# RGB_i2c_v2plusRTC.net
KiCad netlist of a schematic drawn in EAGLE
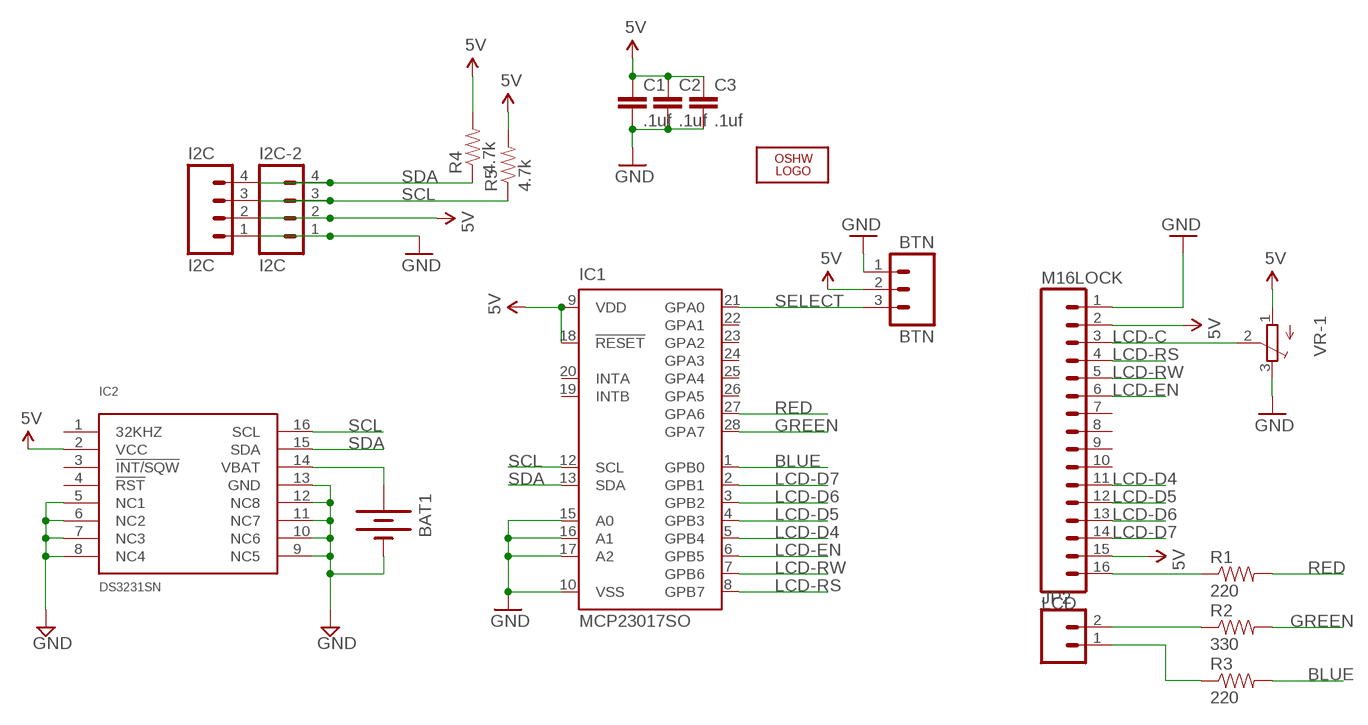
[diagram p0: schematic, sheet 1]

(export (version "E")
  (design (tool "Eeschema 10.0.6"))
  (components
    (comp (ref "BAT1")
      (value "BATTERY12MM")
      (footprint "eagle-import:BATTCON_12MM")
      (libsource (lib "eagle-import") (part "BATTERY12MM"))
    )
    (comp (ref "BTN")
      (value "BTN")
      (footprint "eagle-import:1X03_LOCK")
      (libsource (lib "eagle-import") (part "M03LOCK"))
    )
    (comp (ref "C1")
      (value ".1uf")
      (footprint "eagle-import:0805")
      (libsource (lib "eagle-import") (part "CAP0805"))
    )
    (comp (ref "C2")
      (value ".1uf")
      (footprint "eagle-import:0805")
      (libsource (lib "eagle-import") (part "CAP0805"))
    )
    (comp (ref "C3")
      (value ".1uf")
      (footprint "eagle-import:0805")
      (libsource (lib "eagle-import") (part "CAP0805"))
    )
    (comp (ref "I2C")
      (value "I2C")
      (footprint "eagle-import:1X04_LOCK")
      (libsource (lib "eagle-import") (part "M04LOCK"))
    )
    (comp (ref "I2C-2")
      (value "I2C")
      (footprint "eagle-import:1X04_LOCK")
      (libsource (lib "eagle-import") (part "M04LOCK"))
    )
    (comp (ref "IC1")
      (value "MCP23017SO")
      (footprint "eagle-import:SO28W")
      (libsource (lib "eagle-import") (part "MCP23017SO"))
    )
    (comp (ref "IC2")
      (value "DS3231SN")
      (footprint "eagle-import:SO16W")
      (libsource (lib "eagle-import") (part "DS3231SN"))
    )
    (comp (ref "JP2")
      (value "M02PTH")
      (footprint "eagle-import:1X02")
      (libsource (lib "eagle-import") (part "M02PTH"))
    )
    (comp (ref "LCD")
      (value "M16LOCK")
      (footprint "eagle-import:1X16_LOCK")
      (libsource (lib "eagle-import") (part "M16LOCK"))
    )
    (comp (ref "LOGO2")
      (value "OSHW_LOGO_10MILX0350-NT")
      (footprint "eagle-import:OSHW_10X350_NOTEXT")
      (libsource (lib "eagle-import") (part "OSHW_LOGO_10MILX0350-NT"))
    )
    (comp (ref "R1")
      (value "220")
      (footprint "eagle-import:0805")
      (libsource (lib "eagle-import") (part "RESISTOR0805-RES"))
    )
    (comp (ref "R2")
      (value "330")
      (footprint "eagle-import:0805")
      (libsource (lib "eagle-import") (part "RESISTOR0805-RES"))
    )
    (comp (ref "R3")
      (value "220")
      (footprint "eagle-import:0805")
      (libsource (lib "eagle-import") (part "RESISTOR0805-RES"))
    )
    (comp (ref "R4")
      (value "4.7k")
      (footprint "eagle-import:0805")
      (libsource (lib "eagle-import") (part "RESISTOR0805-RES"))
    )
    (comp (ref "R5")
      (value "4.7k")
      (footprint "eagle-import:0805")
      (libsource (lib "eagle-import") (part "RESISTOR0805-RES"))
    )
    (comp (ref "VR-1")
      (value "TRIMPOTTC33X")
      (footprint "eagle-import:TC33X")
      (libsource (lib "eagle-import") (part "TRIMPOTTC33X"))
    )
  )
  (nets
    (net (code "1") (name "/BLUE") (class "Default")
      (node (ref "IC1") (pin "1") (pinfunction "GPB0_1") (pintype "bidirectional"))
      (node (ref "R3") (pin "2") (pinfunction "2_2") (pintype "passive"))
    )
    (net (code "2") (name "/GREEN") (class "Default")
      (node (ref "IC1") (pin "28") (pinfunction "GPA7_28") (pintype "bidirectional"))
      (node (ref "R2") (pin "2") (pinfunction "2_2") (pintype "passive"))
    )
    (net (code "3") (name "/LCD-C") (class "Default")
      (node (ref "LCD") (pin "3") (pinfunction "3_3") (pintype "passive"))
      (node (ref "VR-1") (pin "2") (pinfunction "S_2") (pintype "passive"))
    )
    (net (code "4") (name "/LCD-D4") (class "Default")
      (node (ref "IC1") (pin "5") (pinfunction "GPB4_5") (pintype "bidirectional"))
      (node (ref "LCD") (pin "11") (pinfunction "11_11") (pintype "passive"))
    )
    (net (code "5") (name "/LCD-D5") (class "Default")
      (node (ref "IC1") (pin "4") (pinfunction "GPB3_4") (pintype "bidirectional"))
      (node (ref "LCD") (pin "12") (pinfunction "12_12") (pintype "passive"))
    )
    (net (code "6") (name "/LCD-D6") (class "Default")
      (node (ref "IC1") (pin "3") (pinfunction "GPB2_3") (pintype "bidirectional"))
      (node (ref "LCD") (pin "13") (pinfunction "13_13") (pintype "passive"))
    )
    (net (code "7") (name "/LCD-D7") (class "Default")
      (node (ref "IC1") (pin "2") (pinfunction "GPB1_2") (pintype "bidirectional"))
      (node (ref "LCD") (pin "14") (pinfunction "14_14") (pintype "passive"))
    )
    (net (code "8") (name "/LCD-EN") (class "Default")
      (node (ref "IC1") (pin "6") (pinfunction "GPB5_6") (pintype "bidirectional"))
      (node (ref "LCD") (pin "6") (pinfunction "6_6") (pintype "passive"))
    )
    (net (code "9") (name "/LCD-RS") (class "Default")
      (node (ref "IC1") (pin "8") (pinfunction "GPB7_8") (pintype "bidirectional"))
      (node (ref "LCD") (pin "4") (pinfunction "4_4") (pintype "passive"))
    )
    (net (code "10") (name "/LCD-RW") (class "Default")
      (node (ref "IC1") (pin "7") (pinfunction "GPB6_7") (pintype "bidirectional"))
      (node (ref "LCD") (pin "5") (pinfunction "5_5") (pintype "passive"))
    )
    (net (code "11") (name "/RED") (class "Default")
      (node (ref "IC1") (pin "27") (pinfunction "GPA6_27") (pintype "bidirectional"))
      (node (ref "R1") (pin "2") (pinfunction "2_2") (pintype "passive"))
    )
    (net (code "12") (name "/SCL") (class "Default")
      (node (ref "I2C") (pin "3") (pinfunction "3_3") (pintype "passive"))
      (node (ref "I2C-2") (pin "3") (pinfunction "3_3") (pintype "passive"))
      (node (ref "IC1") (pin "12") (pinfunction "SCL_12") (pintype "input"))
      (node (ref "IC2") (pin "16") (pinfunction "SCL_16") (pintype "bidirectional"))
      (node (ref "R5") (pin "1") (pinfunction "1_1") (pintype "passive"))
    )
    (net (code "13") (name "/SDA") (class "Default")
      (node (ref "I2C") (pin "4") (pinfunction "4_4") (pintype "passive"))
      (node (ref "I2C-2") (pin "4") (pinfunction "4_4") (pintype "passive"))
      (node (ref "IC1") (pin "13") (pinfunction "SDA_13") (pintype "bidirectional"))
      (node (ref "IC2") (pin "15") (pinfunction "SDA_15") (pintype "bidirectional"))
      (node (ref "R4") (pin "1") (pinfunction "1_1") (pintype "passive"))
    )
    (net (code "14") (name "/SELECT") (class "Default")
      (node (ref "BTN") (pin "3") (pinfunction "3_3") (pintype "passive"))
      (node (ref "IC1") (pin "21") (pinfunction "GPA0_21") (pintype "bidirectional"))
    )
    (net (code "15") (name "5V") (class "Default")
      (node (ref "BTN") (pin "2") (pinfunction "2_2") (pintype "passive"))
      (node (ref "C1") (pin "1") (pinfunction "1_1") (pintype "passive"))
      (node (ref "C2") (pin "1") (pinfunction "1_1") (pintype "passive"))
      (node (ref "C3") (pin "1") (pinfunction "1_1") (pintype "passive"))
      (node (ref "I2C") (pin "2") (pinfunction "2_2") (pintype "passive"))
      (node (ref "I2C-2") (pin "2") (pinfunction "2_2") (pintype "passive"))
      (node (ref "IC1") (pin "18") (pinfunction "~{RESET}_18") (pintype "input"))
      (node (ref "IC1") (pin "9") (pinfunction "VDD_9") (pintype "power_in"))
      (node (ref "IC2") (pin "2") (pinfunction "VCC_2") (pintype "bidirectional"))
      (node (ref "LCD") (pin "15") (pinfunction "15_15") (pintype "passive"))
      (node (ref "LCD") (pin "2") (pinfunction "2_2") (pintype "passive"))
      (node (ref "R4") (pin "2") (pinfunction "2_2") (pintype "passive"))
      (node (ref "R5") (pin "2") (pinfunction "2_2") (pintype "passive"))
      (node (ref "VR-1") (pin "1") (pinfunction "A_1") (pintype "passive"))
    )
    (net (code "16") (name "GND") (class "Default")
      (node (ref "BAT1") (pin "GND") (pinfunction "-_GND") (pintype "power_in"))
      (node (ref "BTN") (pin "1") (pinfunction "1_1") (pintype "passive"))
      (node (ref "C1") (pin "2") (pinfunction "2_2") (pintype "passive"))
      (node (ref "C2") (pin "2") (pinfunction "2_2") (pintype "passive"))
      (node (ref "C3") (pin "2") (pinfunction "2_2") (pintype "passive"))
      (node (ref "I2C") (pin "1") (pinfunction "1_1") (pintype "passive"))
      (node (ref "I2C-2") (pin "1") (pinfunction "1_1") (pintype "passive"))
      (node (ref "IC1") (pin "10") (pinfunction "VSS_10") (pintype "power_in"))
      (node (ref "IC1") (pin "15") (pinfunction "A0_15") (pintype "input"))
      (node (ref "IC1") (pin "16") (pinfunction "A1_16") (pintype "input"))
      (node (ref "IC1") (pin "17") (pinfunction "A2_17") (pintype "input"))
      (node (ref "IC2") (pin "10") (pinfunction "NC6_10") (pintype "bidirectional"))
      (node (ref "IC2") (pin "11") (pinfunction "NC7_11") (pintype "bidirectional"))
      (node (ref "IC2") (pin "12") (pinfunction "NC8_12") (pintype "bidirectional"))
      (node (ref "IC2") (pin "13") (pinfunction "GND_13") (pintype "bidirectional"))
      (node (ref "IC2") (pin "5") (pinfunction "NC1_5") (pintype "bidirectional"))
      (node (ref "IC2") (pin "6") (pinfunction "NC2_6") (pintype "bidirectional"))
      (node (ref "IC2") (pin "7") (pinfunction "NC3_7") (pintype "bidirectional"))
      (node (ref "IC2") (pin "8") (pinfunction "NC4_8") (pintype "bidirectional"))
      (node (ref "IC2") (pin "9") (pinfunction "NC5_9") (pintype "bidirectional"))
      (node (ref "LCD") (pin "1") (pinfunction "1_1") (pintype "passive"))
      (node (ref "VR-1") (pin "3") (pinfunction "E_3") (pintype "passive"))
    )
    (net (code "17") (name "Net-(BAT1-+)") (class "Default")
      (node (ref "BAT1") (pin "PWR@1") (pinfunction "+_PWR@1") (pintype "power_in"))
      (node (ref "IC2") (pin "14") (pinfunction "VBAT_14") (pintype "bidirectional"))
    )
    (net (code "18") (name "Net-(JP2-Pad1)") (class "Default")
      (node (ref "JP2") (pin "1") (pinfunction "1_1") (pintype "passive"))
      (node (ref "R3") (pin "1") (pinfunction "1_1") (pintype "passive"))
    )
    (net (code "19") (name "Net-(JP2-Pad2)") (class "Default")
      (node (ref "JP2") (pin "2") (pinfunction "2_2") (pintype "passive"))
      (node (ref "R2") (pin "1") (pinfunction "1_1") (pintype "passive"))
    )
    (net (code "20") (name "Net-(LCD-Pad16)") (class "Default")
      (node (ref "LCD") (pin "16") (pinfunction "16_16") (pintype "passive"))
      (node (ref "R1") (pin "1") (pinfunction "1_1") (pintype "passive"))
    )
    (net (code "21") (name "unconnected-(IC1-GPA1-Pad22)") (class "Default")
      (node (ref "IC1") (pin "22") (pinfunction "GPA1_22") (pintype "bidirectional"))
    )
    (net (code "22") (name "unconnected-(IC1-GPA2-Pad23)") (class "Default")
      (node (ref "IC1") (pin "23") (pinfunction "GPA2_23") (pintype "bidirectional"))
    )
    (net (code "23") (name "unconnected-(IC1-GPA3-Pad24)") (class "Default")
      (node (ref "IC1") (pin "24") (pinfunction "GPA3_24") (pintype "bidirectional"))
    )
    (net (code "24") (name "unconnected-(IC1-GPA4-Pad25)") (class "Default")
      (node (ref "IC1") (pin "25") (pinfunction "GPA4_25") (pintype "bidirectional"))
    )
    (net (code "25") (name "unconnected-(IC1-GPA5-Pad26)") (class "Default")
      (node (ref "IC1") (pin "26") (pinfunction "GPA5_26") (pintype "bidirectional"))
    )
    (net (code "26") (name "unconnected-(IC1-INTA-Pad20)") (class "Default")
      (node (ref "IC1") (pin "20") (pinfunction "INTA_20") (pintype "output"))
    )
    (net (code "27") (name "unconnected-(IC1-INTB-Pad19)") (class "Default")
      (node (ref "IC1") (pin "19") (pinfunction "INTB_19") (pintype "output"))
    )
    (net (code "28") (name "unconnected-(IC2-32KHZ-Pad1)") (class "Default")
      (node (ref "IC2") (pin "1") (pinfunction "32KHZ_1") (pintype "bidirectional"))
    )
    (net (code "29") (name "unconnected-(IC2-~{INT{slash}SQW}-Pad3)") (class "Default")
      (node (ref "IC2") (pin "3") (pinfunction "~{INT/SQW}_3") (pintype "bidirectional"))
    )
    (net (code "30") (name "unconnected-(IC2-~{RST}-Pad4)") (class "Default")
      (node (ref "IC2") (pin "4") (pinfunction "~{RST}_4") (pintype "bidirectional"))
    )
    (net (code "31") (name "unconnected-(LCD-Pad7)") (class "Default")
      (node (ref "LCD") (pin "7") (pinfunction "7_7") (pintype "passive"))
    )
    (net (code "32") (name "unconnected-(LCD-Pad8)") (class "Default")
      (node (ref "LCD") (pin "8") (pinfunction "8_8") (pintype "passive"))
    )
    (net (code "33") (name "unconnected-(LCD-Pad9)") (class "Default")
      (node (ref "LCD") (pin "9") (pinfunction "9_9") (pintype "passive"))
    )
    (net (code "34") (name "unconnected-(LCD-Pad10)") (class "Default")
      (node (ref "LCD") (pin "10") (pinfunction "10_10") (pintype "passive"))
    )
  )
)
